# S7G7_footprint_simplified_w_ethernet_v1p.net
KiCad netlist of a schematic drawn in EAGLE
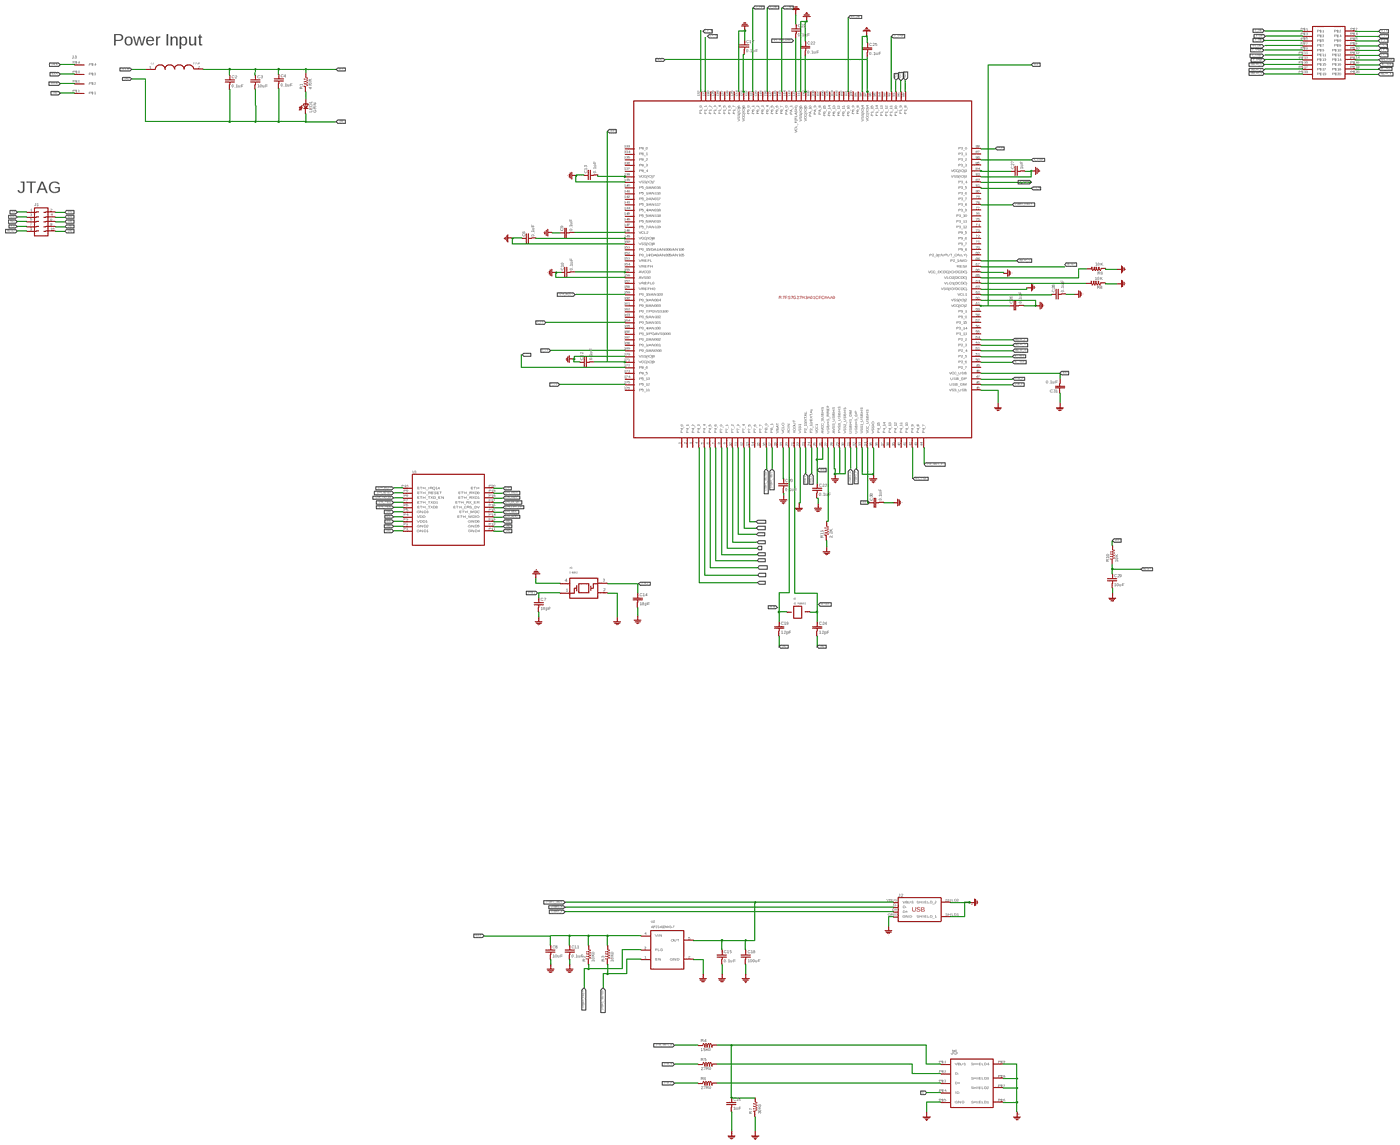
[diagram p0: schematic, sheet 1, overview]
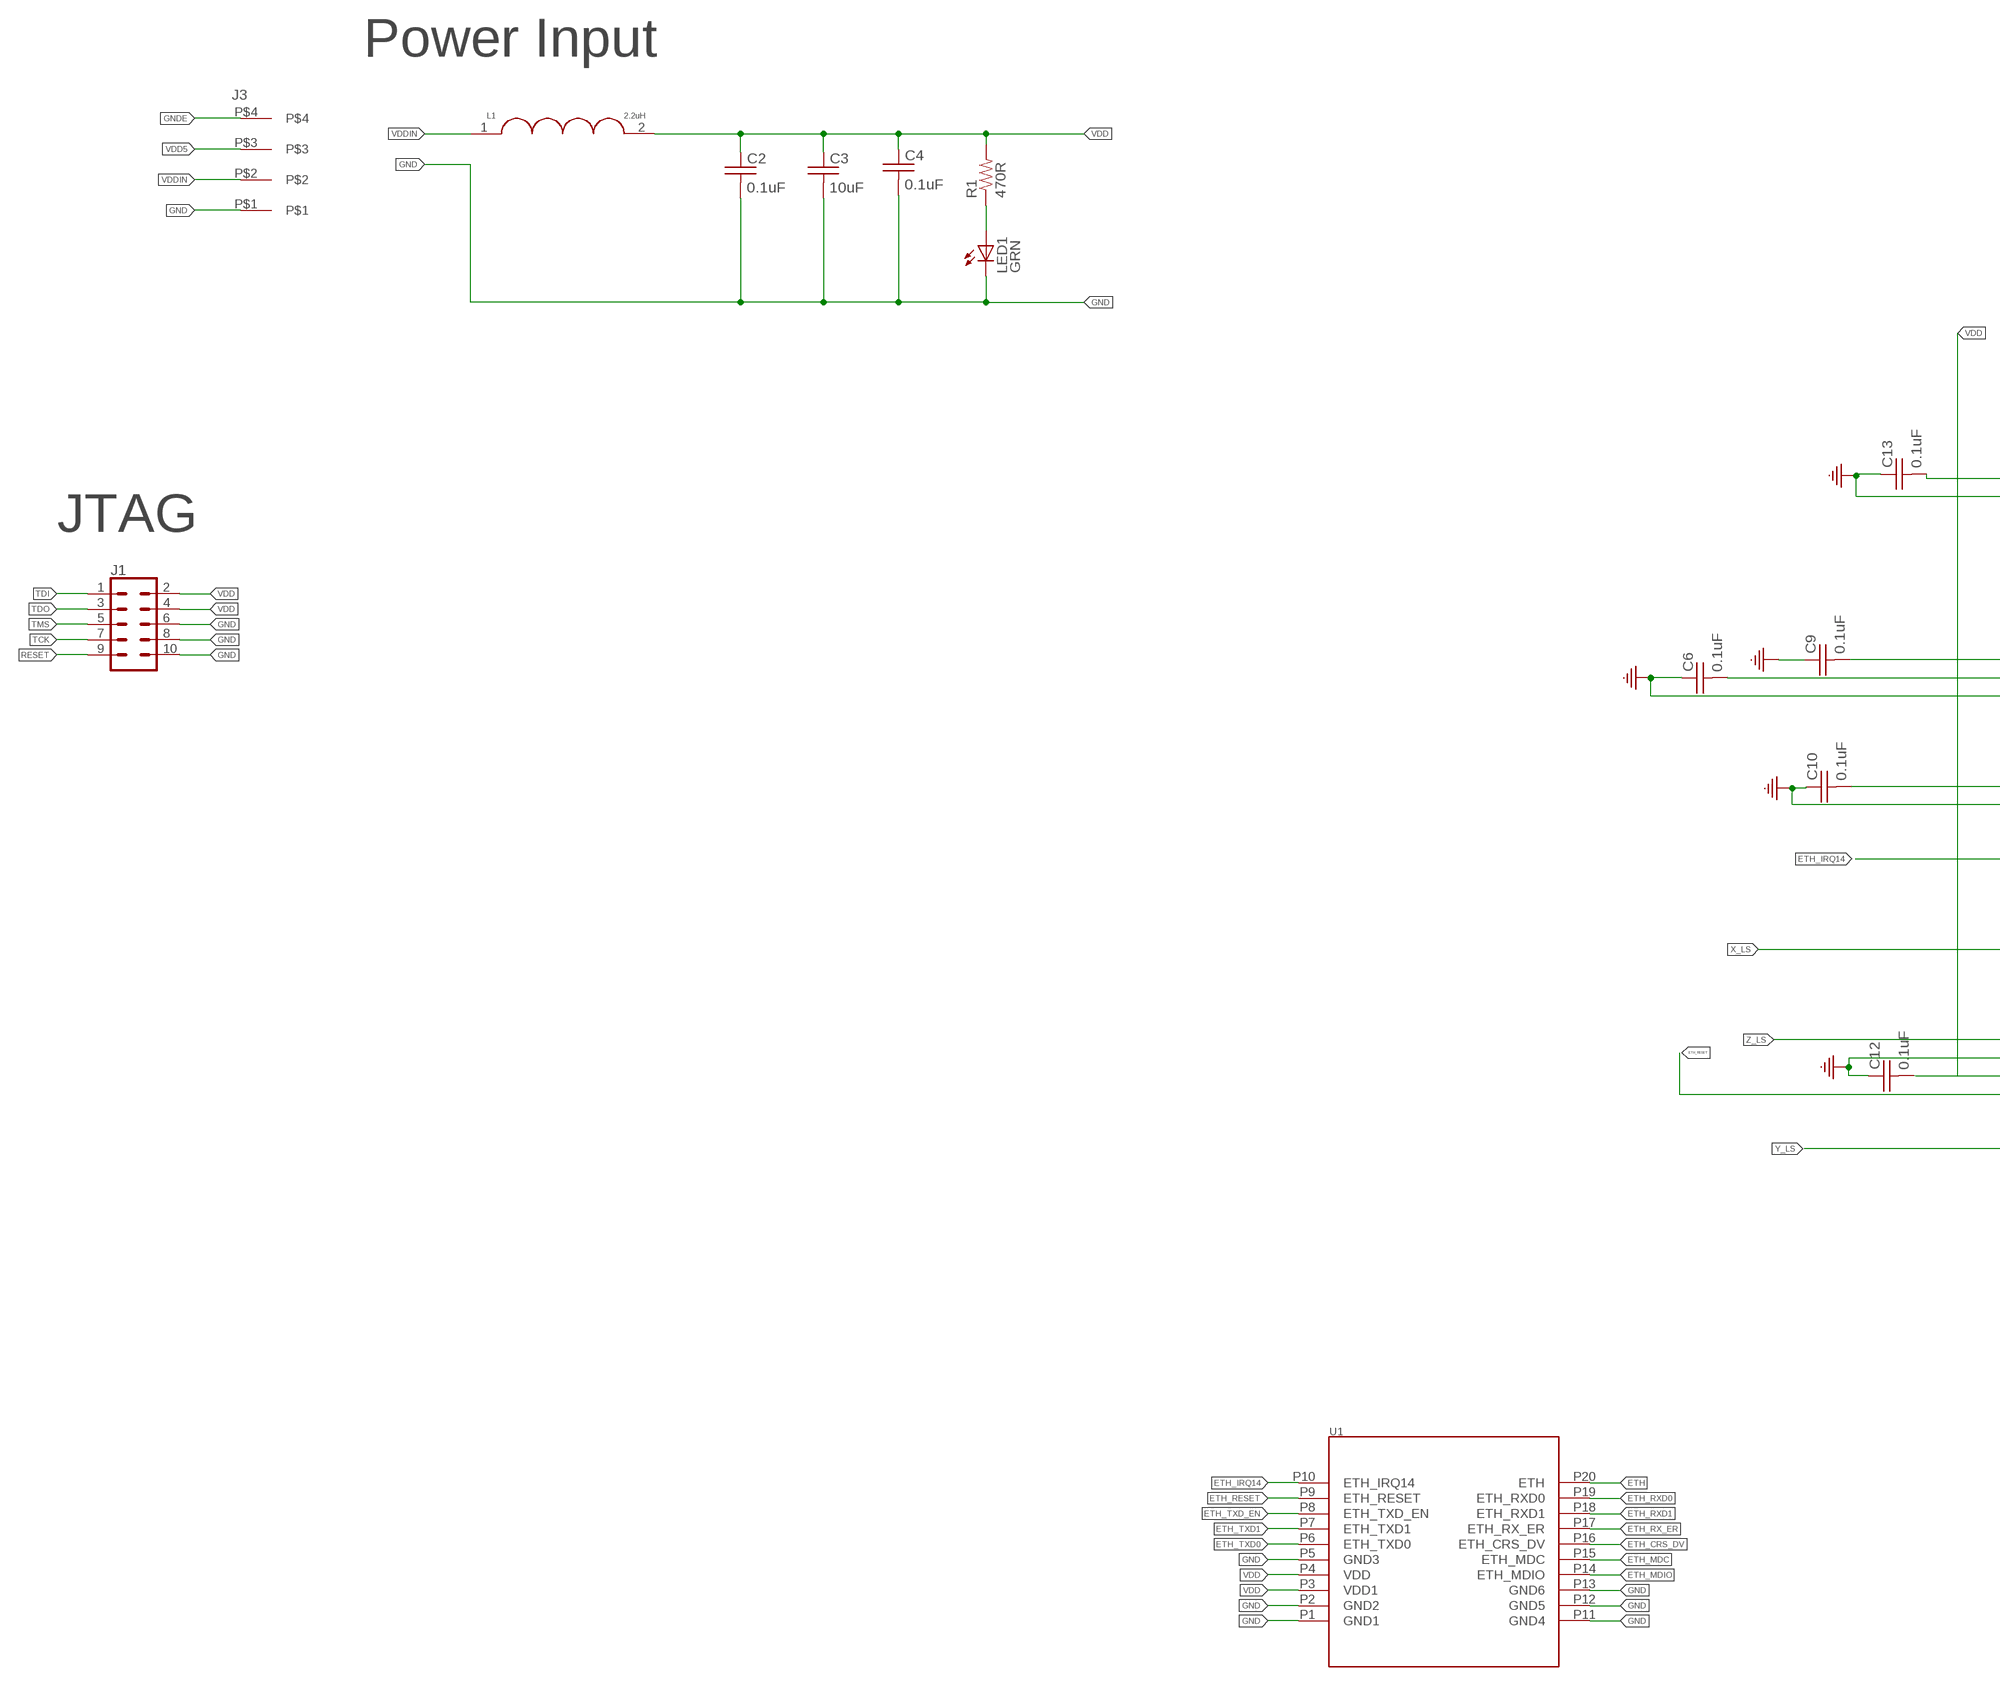
[diagram p1: schematic, sheet 1, part 1 of 4]
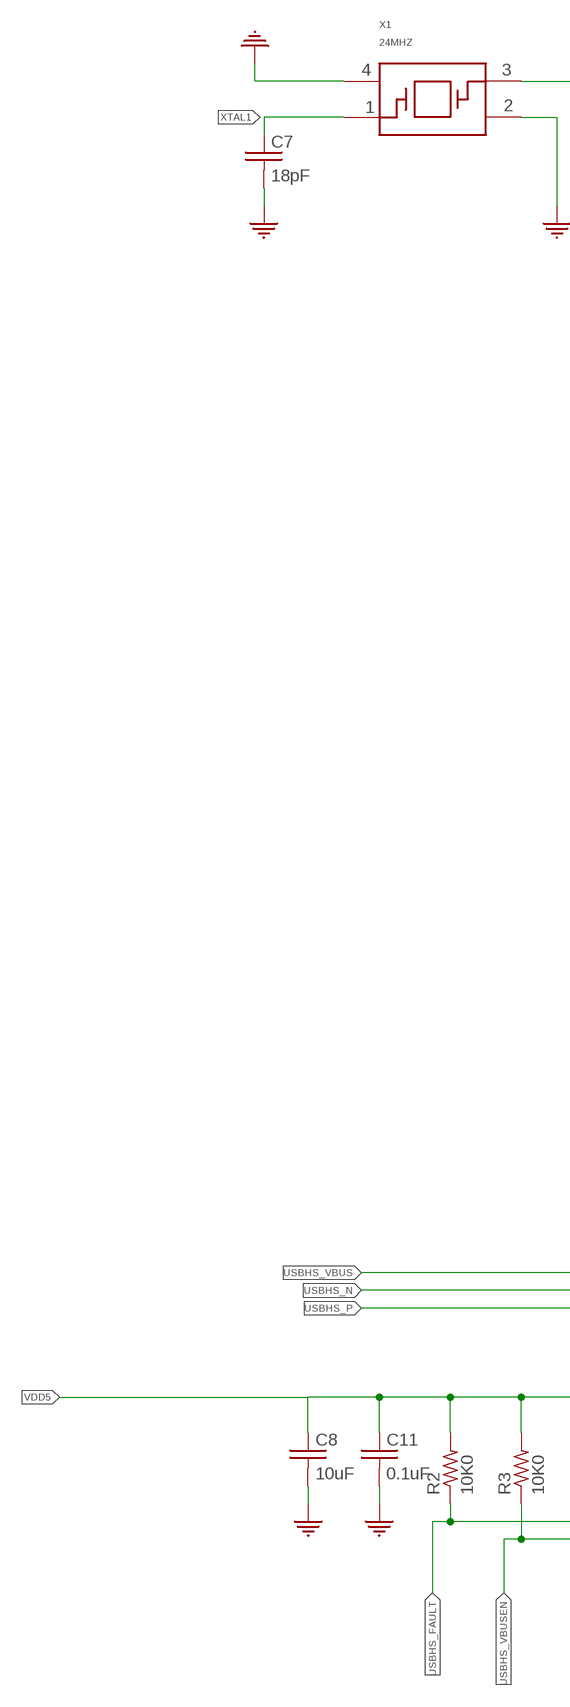
[diagram p2: schematic, sheet 1, part 2 of 4]
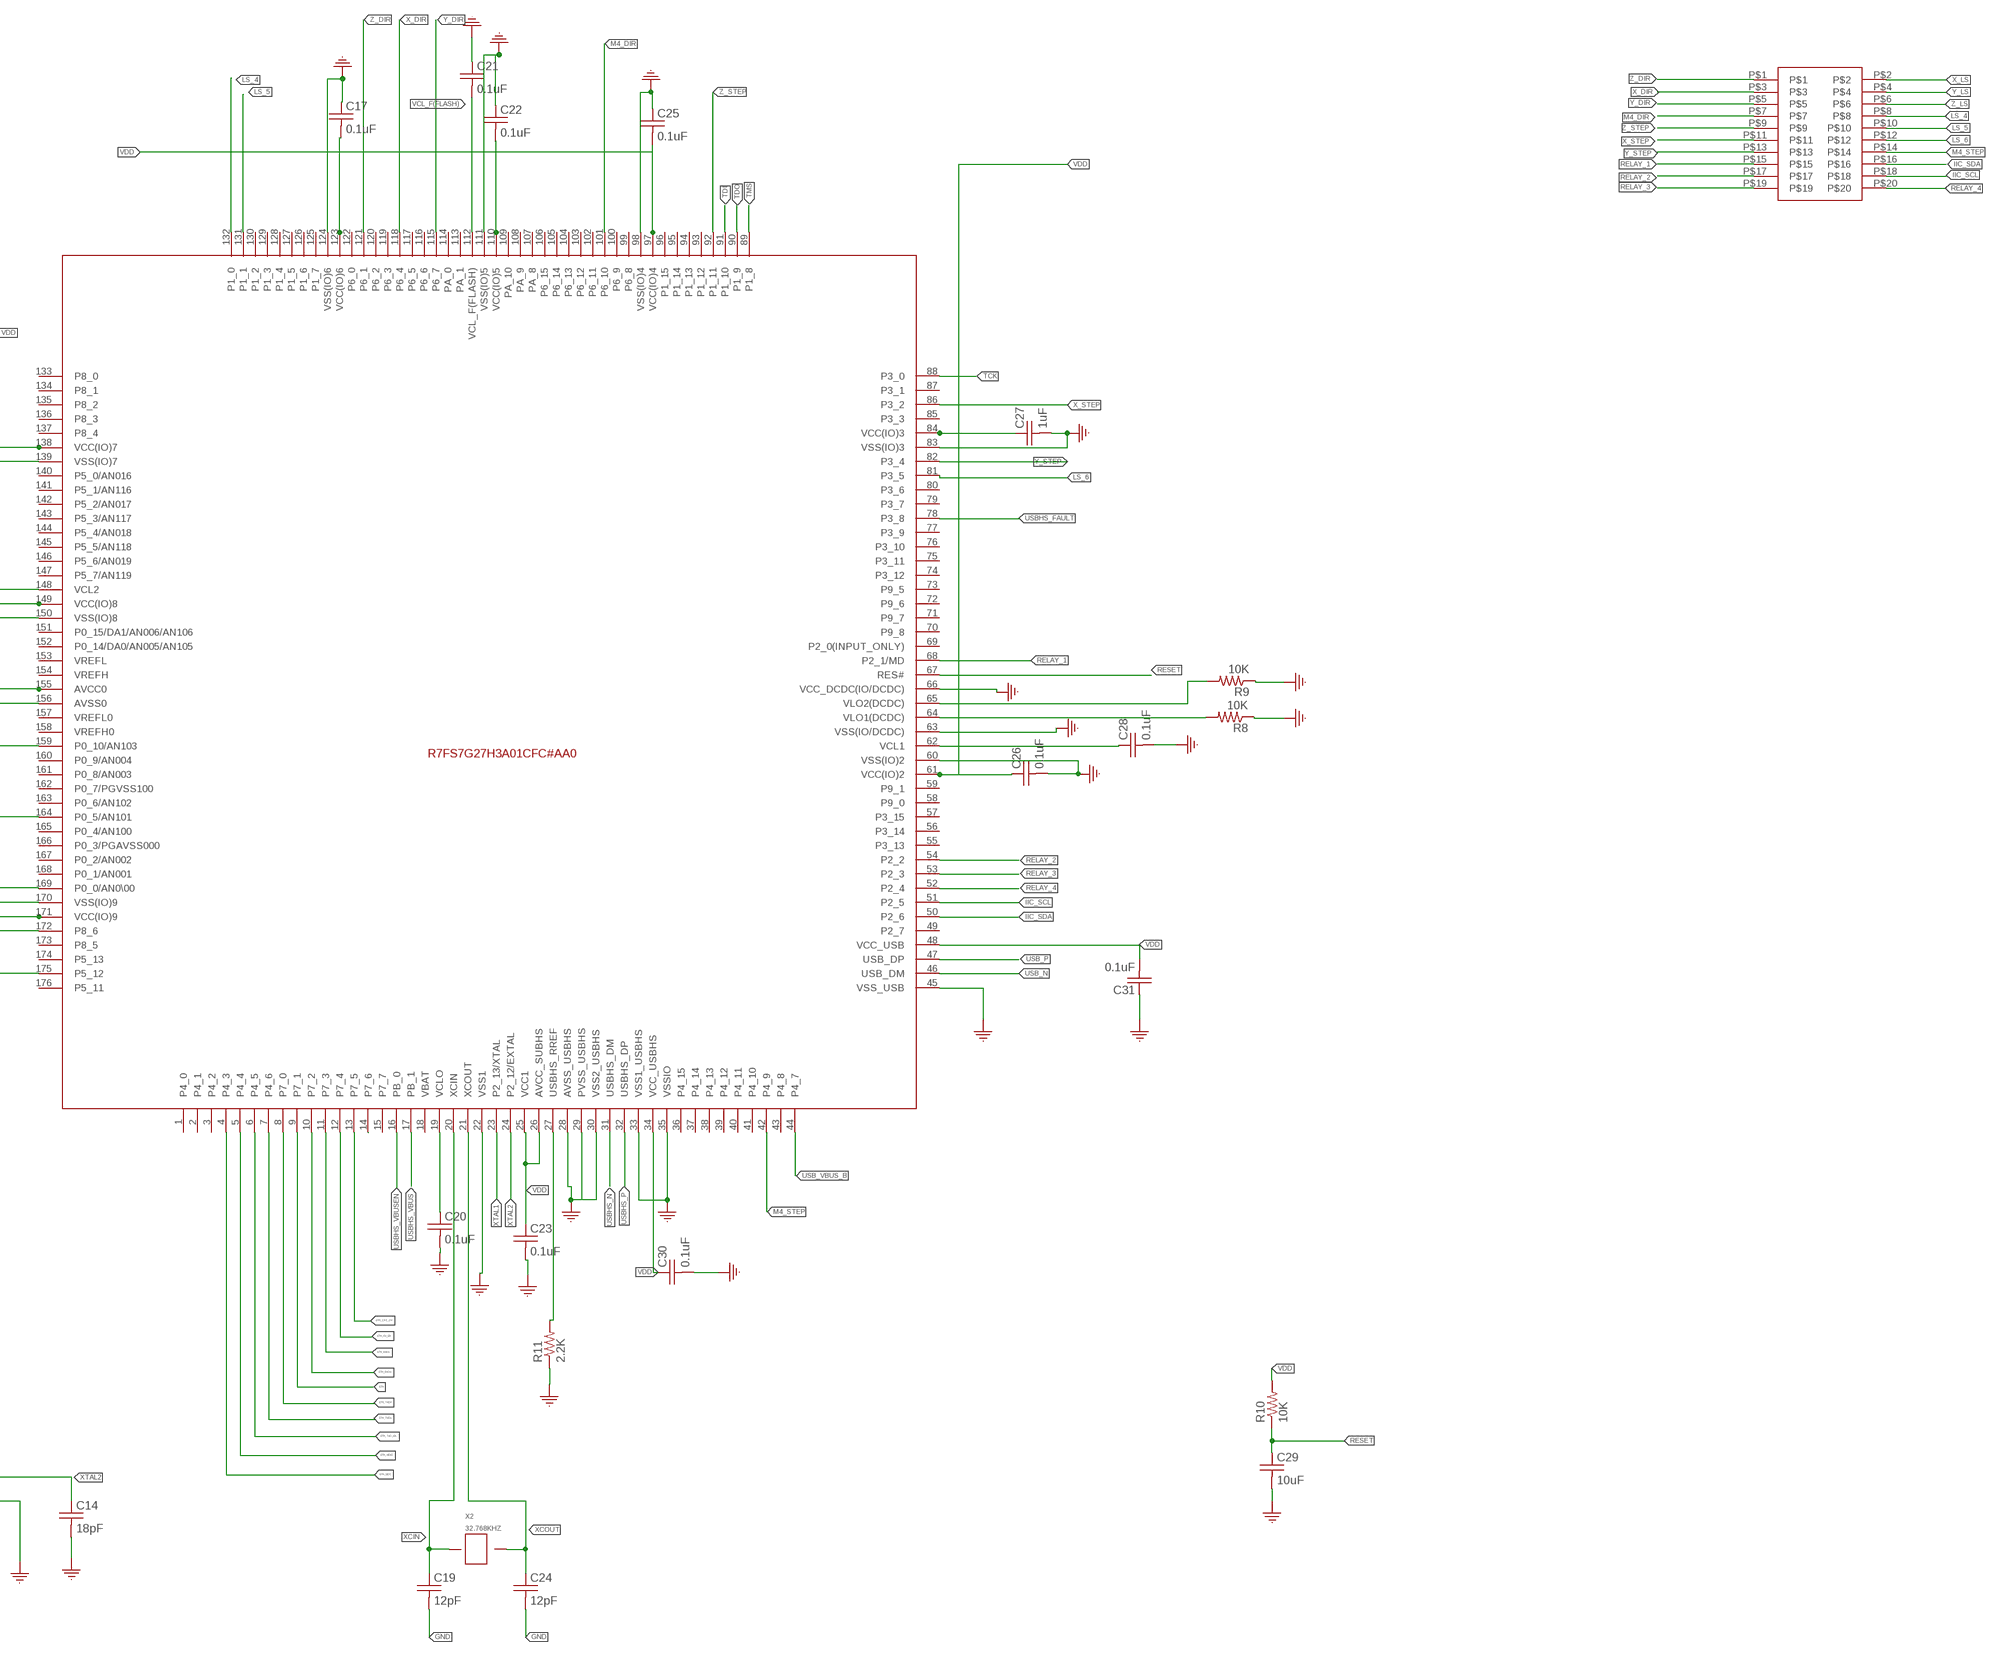
[diagram p3: schematic, sheet 1, part 3 of 4]
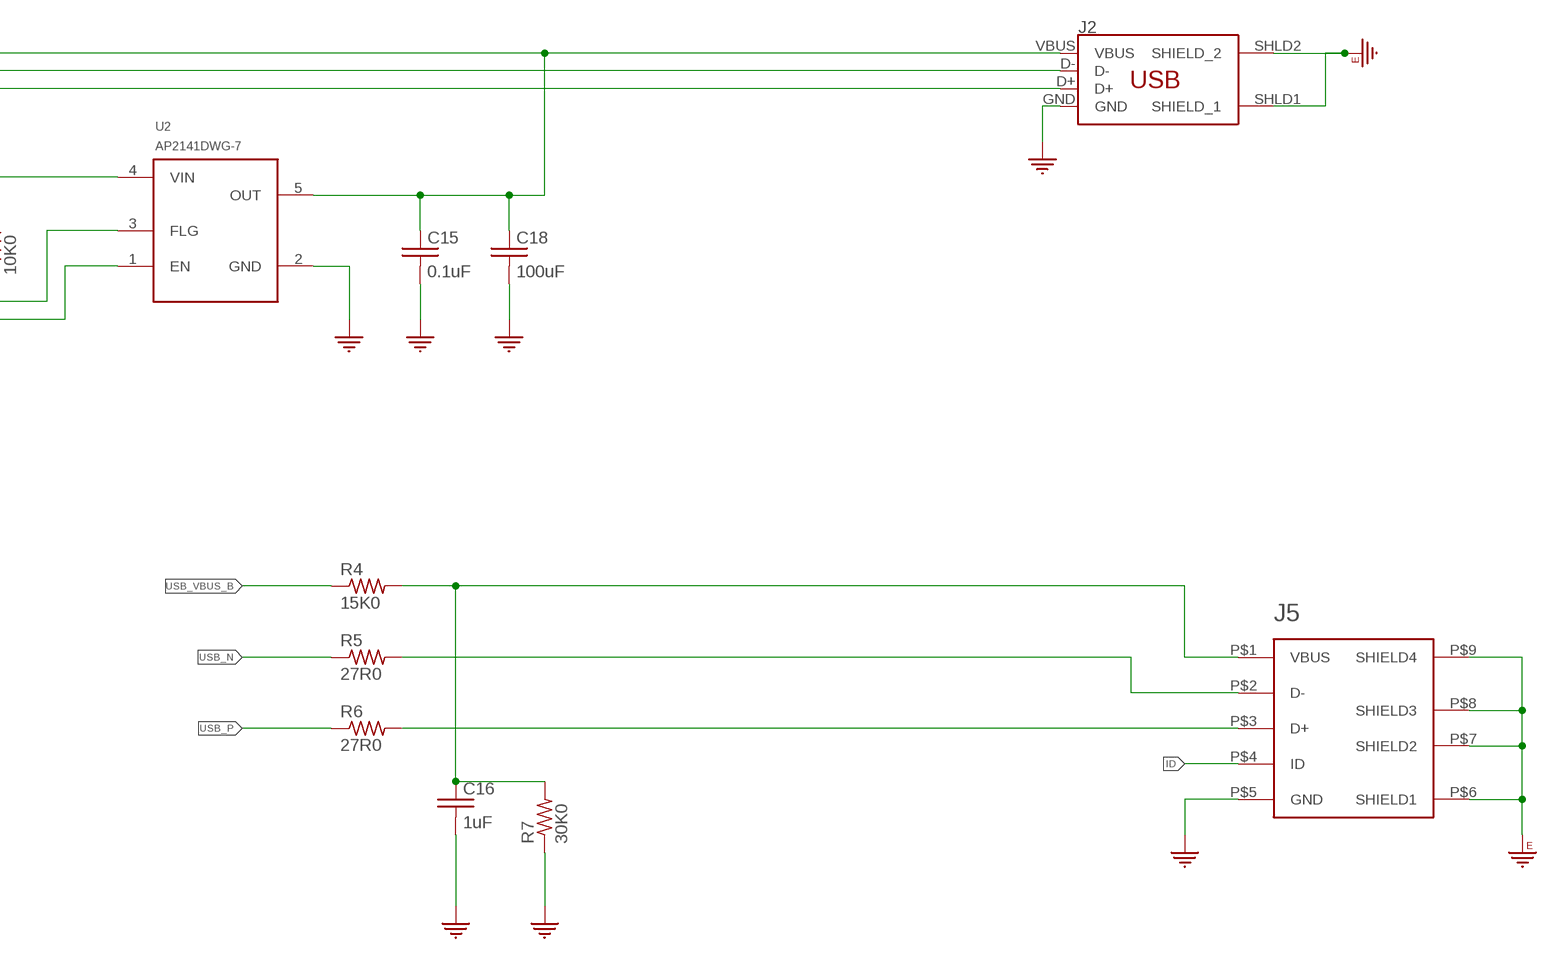
[diagram p4: schematic, sheet 1, part 4 of 4]

(export (version "E")
  (design (tool "Eeschema 10.0.6"))
  (components
    (comp (ref "C2")
      (value "0.1uF")
      (footprint "eagle-import:0402")
      (libsource (lib "eagle-import") (part "C_0402"))
    )
    (comp (ref "C3")
      (value "10uF")
      (footprint "eagle-import:0402")
      (libsource (lib "eagle-import") (part "C_0402"))
    )
    (comp (ref "C4")
      (value "0.1uF")
      (footprint "eagle-import:0402")
      (libsource (lib "eagle-import") (part "C_0402"))
    )
    (comp (ref "C6")
      (value "0.1uF")
      (footprint "eagle-import:0402")
      (libsource (lib "eagle-import") (part "C_0402"))
    )
    (comp (ref "C7")
      (value "18pF")
      (footprint "eagle-import:0402")
      (libsource (lib "eagle-import") (part "C_0402"))
    )
    (comp (ref "C8")
      (value "10uF")
      (footprint "eagle-import:0402")
      (libsource (lib "eagle-import") (part "C_0402"))
    )
    (comp (ref "C9")
      (value "0.1uF")
      (footprint "eagle-import:0402")
      (libsource (lib "eagle-import") (part "C_0402"))
    )
    (comp (ref "C10")
      (value "0.1uF")
      (footprint "eagle-import:0402")
      (libsource (lib "eagle-import") (part "C_0402"))
    )
    (comp (ref "C11")
      (value "0.1uF")
      (footprint "eagle-import:0402")
      (libsource (lib "eagle-import") (part "C_0402"))
    )
    (comp (ref "C12")
      (value "0.1uF")
      (footprint "eagle-import:0402")
      (libsource (lib "eagle-import") (part "C_0402"))
    )
    (comp (ref "C13")
      (value "0.1uF")
      (footprint "eagle-import:0402")
      (libsource (lib "eagle-import") (part "C_0402"))
    )
    (comp (ref "C14")
      (value "18pF")
      (footprint "eagle-import:0402")
      (libsource (lib "eagle-import") (part "C_0402"))
    )
    (comp (ref "C15")
      (value "0.1uF")
      (footprint "eagle-import:0402")
      (libsource (lib "eagle-import") (part "C_0402"))
    )
    (comp (ref "C16")
      (value "1uF")
      (footprint "eagle-import:0402")
      (libsource (lib "eagle-import") (part "C_0402"))
    )
    (comp (ref "C17")
      (value "0.1uF")
      (footprint "eagle-import:0402")
      (libsource (lib "eagle-import") (part "C_0402"))
    )
    (comp (ref "C18")
      (value "100uF")
      (footprint "eagle-import:C1210")
      (libsource (lib "eagle-import") (part "C_1210"))
    )
    (comp (ref "C19")
      (value "12pF")
      (footprint "eagle-import:0402")
      (libsource (lib "eagle-import") (part "C_0402"))
    )
    (comp (ref "C20")
      (value "0.1uF")
      (footprint "eagle-import:0402")
      (libsource (lib "eagle-import") (part "C_0402"))
    )
    (comp (ref "C21")
      (value "0.1uF")
      (footprint "eagle-import:0402")
      (libsource (lib "eagle-import") (part "C_0402"))
    )
    (comp (ref "C22")
      (value "0.1uF")
      (footprint "eagle-import:0402")
      (libsource (lib "eagle-import") (part "C_0402"))
    )
    (comp (ref "C23")
      (value "0.1uF")
      (footprint "eagle-import:0402")
      (libsource (lib "eagle-import") (part "C_0402"))
    )
    (comp (ref "C24")
      (value "12pF")
      (footprint "eagle-import:0402")
      (libsource (lib "eagle-import") (part "C_0402"))
    )
    (comp (ref "C25")
      (value "0.1uF")
      (footprint "eagle-import:0402")
      (libsource (lib "eagle-import") (part "C_0402"))
    )
    (comp (ref "C26")
      (value "0.1uF")
      (footprint "eagle-import:0402")
      (libsource (lib "eagle-import") (part "C_0402"))
    )
    (comp (ref "C27")
      (value "1uF")
      (footprint "eagle-import:0402")
      (libsource (lib "eagle-import") (part "C_0402"))
    )
    (comp (ref "C28")
      (value "0.1uF")
      (footprint "eagle-import:0402")
      (libsource (lib "eagle-import") (part "C_0402"))
    )
    (comp (ref "C29")
      (value "10uF")
      (footprint "eagle-import:0402")
      (libsource (lib "eagle-import") (part "C_0402"))
    )
    (comp (ref "C30")
      (value "0.1uF")
      (footprint "eagle-import:0402")
      (libsource (lib "eagle-import") (part "C_0402"))
    )
    (comp (ref "C31")
      (value "0.1uF")
      (footprint "eagle-import:0402")
      (libsource (lib "eagle-import") (part "C_0402"))
    )
    (comp (ref "J1")
      (value "CONN_05X2PTH")
      (footprint "eagle-import:2X5")
      (libsource (lib "eagle-import") (part "CONN_05X2PTH"))
    )
    (comp (ref "J2")
      (value "USB_A")
      (footprint "eagle-import:USB_A_SMT")
      (libsource (lib "eagle-import") (part "USB_A"))
    )
    (comp (ref "J3")
      (value "3.81MM_1_X_4_RT_ANGLE_PLUG_HEADER")
      (footprint "eagle-import:1X4_3.81MM_PITCH")
      (libsource (lib "eagle-import") (part "3.81MM_1_X_4_RT_ANGLE_PLUG_HEADER"))
    )
    (comp (ref "J4")
      (value "2_X_10_HEADER_GENERIC")
      (footprint "eagle-import:2_X_10_.1_INCH")
      (libsource (lib "eagle-import") (part "2_X_10_HEADER_GENERIC"))
    )
    (comp (ref "J5")
      (value "USB_MICRO-B")
      (footprint "eagle-import:USB_MICRO-B")
      (libsource (lib "eagle-import") (part "USB_MICRO-B"))
    )
    (comp (ref "L1")
      (value "2.2uH")
      (footprint "eagle-import:1008_(2520_METRIC)")
      (libsource (lib "eagle-import") (part "INDUCTOR_1008_2.2_MH_1.3A"))
    )
    (comp (ref "LED1")
      (value "LED_0805_GREEN")
      (footprint "eagle-import:LED_0805_GREEN")
      (libsource (lib "eagle-import") (part "LED_0805_GREEN"))
    )
    (comp (ref "R1")
      (value "470R")
      (footprint "eagle-import:0402")
      (libsource (lib "eagle-import") (part "R_0402"))
    )
    (comp (ref "R2")
      (value "10K0")
      (footprint "eagle-import:0402")
      (libsource (lib "eagle-import") (part "R_0402"))
    )
    (comp (ref "R3")
      (value "10K0")
      (footprint "eagle-import:0402")
      (libsource (lib "eagle-import") (part "R_0402"))
    )
    (comp (ref "R4")
      (value "15K0")
      (footprint "eagle-import:0402")
      (libsource (lib "eagle-import") (part "R_0402"))
    )
    (comp (ref "R5")
      (value "27R0")
      (footprint "eagle-import:0402")
      (libsource (lib "eagle-import") (part "R_0402"))
    )
    (comp (ref "R6")
      (value "27R0")
      (footprint "eagle-import:0402")
      (libsource (lib "eagle-import") (part "R_0402"))
    )
    (comp (ref "R7")
      (value "30K0")
      (footprint "eagle-import:0402")
      (libsource (lib "eagle-import") (part "R_0402"))
    )
    (comp (ref "R8")
      (value "10K")
      (footprint "eagle-import:0402")
      (libsource (lib "eagle-import") (part "R_0402"))
    )
    (comp (ref "R9")
      (value "10K")
      (footprint "eagle-import:0402")
      (libsource (lib "eagle-import") (part "R_0402"))
    )
    (comp (ref "R10")
      (value "10K")
      (footprint "eagle-import:0402")
      (libsource (lib "eagle-import") (part "R_0402"))
    )
    (comp (ref "R11")
      (value "2.2K")
      (footprint "eagle-import:0402")
      (libsource (lib "eagle-import") (part "R_0402"))
    )
    (comp (ref "U1")
      (value "ETHERNET_HAT")
      (footprint "eagle-import:ETHERNET_HAT")
      (libsource (lib "eagle-import") (part "ETHERNET_HAT"))
    )
    (comp (ref "U2")
      (value "AP2141DWG-5")
      (footprint "eagle-import:SOT-23-5")
      (libsource (lib "eagle-import") (part "AP2141DWG-5"))
    )
    (comp (ref "U5")
      (value "S7G2_X_176")
      (footprint "eagle-import:LQFP176_24X24")
      (libsource (lib "eagle-import") (part "S7G2_X_176"))
    )
    (comp (ref "X1")
      (value "24MHZ")
      (footprint "eagle-import:SMD_3225")
      (libsource (lib "eagle-import") (part "XTAL_24_MHZ"))
    )
    (comp (ref "X2")
      (value "32.768KHZ")
      (footprint "eagle-import:SMD_X_2_PADS")
      (libsource (lib "eagle-import") (part "XTAL_32.768KHZ"))
    )
  )
  (nets
    (net (code "1") (name "ETH") (class "Default")
      (node (ref "U1") (pin "P20") (pinfunction "ETH_P20") (pintype "bidirectional"))
      (node (ref "U5") (pin "9") (pinfunction "P7_1_9") (pintype "bidirectional"))
    )
    (net (code "2") (name "ETH_CRS_DV") (class "Default")
      (node (ref "U1") (pin "P16") (pinfunction "ETH_CRS_DV_P16") (pintype "bidirectional"))
      (node (ref "U5") (pin "13") (pinfunction "P7_5_13") (pintype "bidirectional"))
    )
    (net (code "3") (name "ETH_IRQ14") (class "Default")
      (node (ref "U1") (pin "P10") (pinfunction "ETH_IRQ14_P10") (pintype "bidirectional"))
      (node (ref "U5") (pin "159") (pinfunction "P0_10/AN103_159") (pintype "bidirectional"))
    )
    (net (code "4") (name "ETH_MDC") (class "Default")
      (node (ref "U1") (pin "P15") (pinfunction "ETH_MDC_P15") (pintype "bidirectional"))
      (node (ref "U5") (pin "4") (pinfunction "P4_3_4") (pintype "bidirectional"))
    )
    (net (code "5") (name "ETH_MDIO") (class "Default")
      (node (ref "U1") (pin "P14") (pinfunction "ETH_MDIO_P14") (pintype "bidirectional"))
      (node (ref "U5") (pin "5") (pinfunction "P4_4_5") (pintype "bidirectional"))
    )
    (net (code "6") (name "ETH_RESET") (class "Default")
      (node (ref "U1") (pin "P9") (pinfunction "ETH_RESET_P9") (pintype "bidirectional"))
      (node (ref "U5") (pin "172") (pinfunction "P8_6_172") (pintype "bidirectional"))
    )
    (net (code "7") (name "ETH_RXD0") (class "Default")
      (node (ref "U1") (pin "P19") (pinfunction "ETH_RXD0_P19") (pintype "bidirectional"))
      (node (ref "U5") (pin "10") (pinfunction "P7_2_10") (pintype "bidirectional"))
    )
    (net (code "8") (name "ETH_RXD1") (class "Default")
      (node (ref "U1") (pin "P18") (pinfunction "ETH_RXD1_P18") (pintype "bidirectional"))
      (node (ref "U5") (pin "11") (pinfunction "P7_3_11") (pintype "bidirectional"))
    )
    (net (code "9") (name "ETH_RX_ER") (class "Default")
      (node (ref "U1") (pin "P17") (pinfunction "ETH_RX_ER_P17") (pintype "bidirectional"))
      (node (ref "U5") (pin "12") (pinfunction "P7_4_12") (pintype "bidirectional"))
    )
    (net (code "10") (name "ETH_TXD0") (class "Default")
      (node (ref "U1") (pin "P6") (pinfunction "ETH_TXD0_P6") (pintype "bidirectional"))
      (node (ref "U5") (pin "8") (pinfunction "P7_0_8") (pintype "bidirectional"))
    )
    (net (code "11") (name "ETH_TXD1") (class "Default")
      (node (ref "U1") (pin "P7") (pinfunction "ETH_TXD1_P7") (pintype "bidirectional"))
      (node (ref "U5") (pin "7") (pinfunction "P4_6_7") (pintype "bidirectional"))
    )
    (net (code "12") (name "ETH_TXD_EN") (class "Default")
      (node (ref "U1") (pin "P8") (pinfunction "ETH_TXD_EN_P8") (pintype "bidirectional"))
      (node (ref "U5") (pin "6") (pinfunction "P4_5_6") (pintype "bidirectional"))
    )
    (net (code "13") (name "GND") (class "Default")
      (node (ref "C10") (pin "P$1") (pinfunction "1_P$1") (pintype "passive"))
      (node (ref "C11") (pin "P$2") (pinfunction "2_P$2") (pintype "passive"))
      (node (ref "C12") (pin "P$1") (pinfunction "1_P$1") (pintype "passive"))
      (node (ref "C13") (pin "P$1") (pinfunction "1_P$1") (pintype "passive"))
      (node (ref "C14") (pin "P$2") (pinfunction "2_P$2") (pintype "passive"))
      (node (ref "C15") (pin "P$2") (pinfunction "2_P$2") (pintype "passive"))
      (node (ref "C16") (pin "P$2") (pinfunction "2_P$2") (pintype "passive"))
      (node (ref "C17") (pin "P$1") (pinfunction "1_P$1") (pintype "passive"))
      (node (ref "C18") (pin "2") (pinfunction "2_2") (pintype "passive"))
      (node (ref "C19") (pin "P$2") (pinfunction "2_P$2") (pintype "passive"))
      (node (ref "C2") (pin "P$2") (pinfunction "2_P$2") (pintype "passive"))
      (node (ref "C20") (pin "P$2") (pinfunction "2_P$2") (pintype "passive"))
      (node (ref "C21") (pin "P$1") (pinfunction "1_P$1") (pintype "passive"))
      (node (ref "C22") (pin "P$1") (pinfunction "1_P$1") (pintype "passive"))
      (node (ref "C23") (pin "P$2") (pinfunction "2_P$2") (pintype "passive"))
      (node (ref "C24") (pin "P$2") (pinfunction "2_P$2") (pintype "passive"))
      (node (ref "C25") (pin "P$1") (pinfunction "1_P$1") (pintype "passive"))
      (node (ref "C26") (pin "P$2") (pinfunction "2_P$2") (pintype "passive"))
      (node (ref "C27") (pin "P$2") (pinfunction "2_P$2") (pintype "passive"))
      (node (ref "C28") (pin "P$2") (pinfunction "2_P$2") (pintype "passive"))
      (node (ref "C29") (pin "P$2") (pinfunction "2_P$2") (pintype "passive"))
      (node (ref "C3") (pin "P$2") (pinfunction "2_P$2") (pintype "passive"))
      (node (ref "C30") (pin "P$2") (pinfunction "2_P$2") (pintype "passive"))
      (node (ref "C31") (pin "P$1") (pinfunction "1_P$1") (pintype "passive"))
      (node (ref "C4") (pin "P$2") (pinfunction "2_P$2") (pintype "passive"))
      (node (ref "C6") (pin "P$1") (pinfunction "1_P$1") (pintype "passive"))
      (node (ref "C7") (pin "P$2") (pinfunction "2_P$2") (pintype "passive"))
      (node (ref "C8") (pin "P$2") (pinfunction "2_P$2") (pintype "passive"))
      (node (ref "C9") (pin "P$1") (pinfunction "1_P$1") (pintype "passive"))
      (node (ref "J1") (pin "10") (pinfunction "10_10") (pintype "passive"))
      (node (ref "J1") (pin "6") (pinfunction "6_6") (pintype "passive"))
      (node (ref "J1") (pin "8") (pinfunction "8_8") (pintype "passive"))
      (node (ref "J2") (pin "GND") (pinfunction "GND_GND") (pintype "power_in"))
      (node (ref "J3") (pin "P$1") (pinfunction "P$1_P$1") (pintype "bidirectional"))
      (node (ref "J5") (pin "P$5") (pinfunction "GND_P$5") (pintype "bidirectional"))
      (node (ref "LED1") (pin "C") (pinfunction "C_C") (pintype "passive"))
      (node (ref "R11") (pin "P$1") (pinfunction "1_P$1") (pintype "passive"))
      (node (ref "R7") (pin "P$1") (pinfunction "1_P$1") (pintype "passive"))
      (node (ref "R8") (pin "P$1") (pinfunction "1_P$1") (pintype "passive"))
      (node (ref "R9") (pin "P$1") (pinfunction "1_P$1") (pintype "passive"))
      (node (ref "U1") (pin "P1") (pinfunction "GND1_P1") (pintype "bidirectional"))
      (node (ref "U1") (pin "P11") (pinfunction "GND4_P11") (pintype "bidirectional"))
      (node (ref "U1") (pin "P12") (pinfunction "GND5_P12") (pintype "bidirectional"))
      (node (ref "U1") (pin "P13") (pinfunction "GND6_P13") (pintype "bidirectional"))
      (node (ref "U1") (pin "P2") (pinfunction "GND2_P2") (pintype "bidirectional"))
      (node (ref "U1") (pin "P5") (pinfunction "GND3_P5") (pintype "bidirectional"))
      (node (ref "U2") (pin "2") (pinfunction "GND_2") (pintype "input"))
      (node (ref "U5") (pin "111") (pinfunction "VSS(IO)5_111") (pintype "bidirectional"))
      (node (ref "U5") (pin "124") (pinfunction "VSS(IO)6_124") (pintype "bidirectional"))
      (node (ref "U5") (pin "139") (pinfunction "VSS(IO)7_139") (pintype "bidirectional"))
      (node (ref "U5") (pin "150") (pinfunction "VSS(IO)8_150") (pintype "bidirectional"))
      (node (ref "U5") (pin "156") (pinfunction "AVSS0_156") (pintype "bidirectional"))
      (node (ref "U5") (pin "170") (pinfunction "VSS(IO)9_170") (pintype "bidirectional"))
      (node (ref "U5") (pin "22") (pinfunction "VSS1_22") (pintype "bidirectional"))
      (node (ref "U5") (pin "28") (pinfunction "AVSS_USBHS_28") (pintype "bidirectional"))
      (node (ref "U5") (pin "29") (pinfunction "PVSS_USBHS_29") (pintype "bidirectional"))
      (node (ref "U5") (pin "30") (pinfunction "VSS2_USBHS_30") (pintype "bidirectional"))
      (node (ref "U5") (pin "33") (pinfunction "VSS1_USBHS_33") (pintype "bidirectional"))
      (node (ref "U5") (pin "35") (pinfunction "VSSIO_35") (pintype "bidirectional"))
      (node (ref "U5") (pin "45") (pinfunction "VSS_USB_45") (pintype "bidirectional"))
      (node (ref "U5") (pin "60") (pinfunction "VSS(IO)2_60") (pintype "bidirectional"))
      (node (ref "U5") (pin "63") (pinfunction "VSS(IO/DCDC)_63") (pintype "bidirectional"))
      (node (ref "U5") (pin "66") (pinfunction "VCC_DCDC(IO/DCDC)_66") (pintype "bidirectional"))
      (node (ref "U5") (pin "83") (pinfunction "VSS(IO)3_83") (pintype "bidirectional"))
      (node (ref "U5") (pin "98") (pinfunction "VSS(IO)4_98") (pintype "bidirectional"))
      (node (ref "X1") (pin "2") (pinfunction "2_2") (pintype "bidirectional"))
      (node (ref "X1") (pin "4") (pinfunction "4_4") (pintype "bidirectional"))
    )
    (net (code "14") (name "GNDE") (class "Default")
      (node (ref "J2") (pin "SHLD1") (pinfunction "SHIELD_1_SHLD1") (pintype "bidirectional"))
      (node (ref "J2") (pin "SHLD2") (pinfunction "SHIELD_2_SHLD2") (pintype "bidirectional"))
      (node (ref "J3") (pin "P$4") (pinfunction "P$4_P$4") (pintype "bidirectional"))
      (node (ref "J5") (pin "P$6") (pinfunction "SHIELD1_P$6") (pintype "bidirectional"))
      (node (ref "J5") (pin "P$7") (pinfunction "SHIELD2_P$7") (pintype "bidirectional"))
      (node (ref "J5") (pin "P$8") (pinfunction "SHIELD3_P$8") (pintype "bidirectional"))
      (node (ref "J5") (pin "P$9") (pinfunction "SHIELD4_P$9") (pintype "bidirectional"))
    )
    (net (code "15") (name "ID") (class "Default")
      (node (ref "J5") (pin "P$4") (pinfunction "ID_P$4") (pintype "bidirectional"))
    )
    (net (code "16") (name "IIC_SCL") (class "Default")
      (node (ref "J4") (pin "P$18") (pinfunction "P$18_P$18") (pintype "bidirectional"))
      (node (ref "U5") (pin "51") (pinfunction "P2_5_51") (pintype "bidirectional"))
    )
    (net (code "17") (name "IIC_SDA") (class "Default")
      (node (ref "J4") (pin "P$16") (pinfunction "P$16_P$16") (pintype "bidirectional"))
      (node (ref "U5") (pin "50") (pinfunction "P2_6_50") (pintype "bidirectional"))
    )
    (net (code "18") (name "LS_4") (class "Default")
      (node (ref "J4") (pin "P$8") (pinfunction "P$8_P$8") (pintype "bidirectional"))
      (node (ref "U5") (pin "132") (pinfunction "P1_0_132") (pintype "bidirectional"))
    )
    (net (code "19") (name "LS_5") (class "Default")
      (node (ref "J4") (pin "P$10") (pinfunction "P$10_P$10") (pintype "bidirectional"))
      (node (ref "U5") (pin "131") (pinfunction "P1_1_131") (pintype "bidirectional"))
    )
    (net (code "20") (name "LS_6") (class "Default")
      (node (ref "J4") (pin "P$12") (pinfunction "P$12_P$12") (pintype "bidirectional"))
      (node (ref "U5") (pin "81") (pinfunction "P3_5_81") (pintype "bidirectional"))
    )
    (net (code "21") (name "M4_DIR") (class "Default")
      (node (ref "J4") (pin "P$7") (pinfunction "P$7_P$7") (pintype "bidirectional"))
      (node (ref "U5") (pin "101") (pinfunction "P6_10_101") (pintype "bidirectional"))
    )
    (net (code "22") (name "M4_STEP") (class "Default")
      (node (ref "J4") (pin "P$14") (pinfunction "P$14_P$14") (pintype "bidirectional"))
      (node (ref "U5") (pin "42") (pinfunction "P4_9_42") (pintype "bidirectional"))
    )
    (net (code "23") (name "Net-(C9-2)") (class "Default")
      (node (ref "C9") (pin "P$2") (pinfunction "2_P$2") (pintype "passive"))
      (node (ref "U5") (pin "148") (pinfunction "VCL2_148") (pintype "bidirectional"))
    )
    (net (code "24") (name "Net-(C16-1)") (class "Default")
      (node (ref "C16") (pin "P$1") (pinfunction "1_P$1") (pintype "passive"))
      (node (ref "J5") (pin "P$1") (pinfunction "VBUS_P$1") (pintype "bidirectional"))
      (node (ref "R4") (pin "P$2") (pinfunction "2_P$2") (pintype "passive"))
      (node (ref "R7") (pin "P$2") (pinfunction "2_P$2") (pintype "passive"))
    )
    (net (code "25") (name "Net-(C20-1)") (class "Default")
      (node (ref "C20") (pin "P$1") (pinfunction "1_P$1") (pintype "passive"))
      (node (ref "U5") (pin "19") (pinfunction "VCLO_19") (pintype "bidirectional"))
    )
    (net (code "26") (name "Net-(C28-1)") (class "Default")
      (node (ref "C28") (pin "P$1") (pinfunction "1_P$1") (pintype "passive"))
      (node (ref "U5") (pin "62") (pinfunction "VCL1_62") (pintype "bidirectional"))
    )
    (net (code "27") (name "Net-(J5-D+)") (class "Default")
      (node (ref "J5") (pin "P$3") (pinfunction "D+_P$3") (pintype "bidirectional"))
      (node (ref "R6") (pin "P$2") (pinfunction "2_P$2") (pintype "passive"))
    )
    (net (code "28") (name "Net-(J5-D-)") (class "Default")
      (node (ref "J5") (pin "P$2") (pinfunction "D-_P$2") (pintype "bidirectional"))
      (node (ref "R5") (pin "P$2") (pinfunction "2_P$2") (pintype "passive"))
    )
    (net (code "29") (name "Net-(R1-1)") (class "Default")
      (node (ref "LED1") (pin "A") (pinfunction "A_A") (pintype "passive"))
      (node (ref "R1") (pin "P$1") (pinfunction "1_P$1") (pintype "passive"))
    )
    (net (code "30") (name "Net-(R8-2)") (class "Default")
      (node (ref "R8") (pin "P$2") (pinfunction "2_P$2") (pintype "passive"))
      (node (ref "U5") (pin "64") (pinfunction "VLO1(DCDC)_64") (pintype "bidirectional"))
    )
    (net (code "31") (name "Net-(R9-2)") (class "Default")
      (node (ref "R9") (pin "P$2") (pinfunction "2_P$2") (pintype "passive"))
      (node (ref "U5") (pin "65") (pinfunction "VLO2(DCDC)_65") (pintype "bidirectional"))
    )
    (net (code "32") (name "Net-(R11-2)") (class "Default")
      (node (ref "R11") (pin "P$2") (pinfunction "2_P$2") (pintype "passive"))
      (node (ref "U5") (pin "27") (pinfunction "USBHS_RREF_27") (pintype "bidirectional"))
    )
    (net (code "33") (name "RELAY_1") (class "Default")
      (node (ref "J4") (pin "P$15") (pinfunction "P$15_P$15") (pintype "bidirectional"))
      (node (ref "U5") (pin "68") (pinfunction "P2_1/MD_68") (pintype "bidirectional"))
    )
    (net (code "34") (name "RELAY_2") (class "Default")
      (node (ref "J4") (pin "P$17") (pinfunction "P$17_P$17") (pintype "bidirectional"))
      (node (ref "U5") (pin "54") (pinfunction "P2_2_54") (pintype "bidirectional"))
    )
    (net (code "35") (name "RELAY_3") (class "Default")
      (node (ref "J4") (pin "P$19") (pinfunction "P$19_P$19") (pintype "bidirectional"))
      (node (ref "U5") (pin "53") (pinfunction "P2_3_53") (pintype "bidirectional"))
    )
    (net (code "36") (name "RELAY_4") (class "Default")
      (node (ref "J4") (pin "P$20") (pinfunction "P$20_P$20") (pintype "bidirectional"))
      (node (ref "U5") (pin "52") (pinfunction "P2_4_52") (pintype "bidirectional"))
    )
    (net (code "37") (name "RESET") (class "Default")
      (node (ref "C29") (pin "P$1") (pinfunction "1_P$1") (pintype "passive"))
      (node (ref "J1") (pin "9") (pinfunction "9_9") (pintype "passive"))
      (node (ref "R10") (pin "P$1") (pinfunction "1_P$1") (pintype "passive"))
      (node (ref "U5") (pin "67") (pinfunction "RES#_67") (pintype "bidirectional"))
    )
    (net (code "38") (name "TCK") (class "Default")
      (node (ref "J1") (pin "7") (pinfunction "7_7") (pintype "passive"))
      (node (ref "U5") (pin "88") (pinfunction "P3_0_88") (pintype "bidirectional"))
    )
    (net (code "39") (name "TDI") (class "Default")
      (node (ref "J1") (pin "1") (pinfunction "1_1") (pintype "passive"))
      (node (ref "U5") (pin "91") (pinfunction "P1_10_91") (pintype "bidirectional"))
    )
    (net (code "40") (name "TDO") (class "Default")
      (node (ref "J1") (pin "3") (pinfunction "3_3") (pintype "passive"))
      (node (ref "U5") (pin "90") (pinfunction "P1_9_90") (pintype "bidirectional"))
    )
    (net (code "41") (name "TMS") (class "Default")
      (node (ref "J1") (pin "5") (pinfunction "5_5") (pintype "passive"))
      (node (ref "U5") (pin "89") (pinfunction "P1_8_89") (pintype "bidirectional"))
    )
    (net (code "42") (name "USBHS_FAULT") (class "Default")
      (node (ref "R2") (pin "P$1") (pinfunction "1_P$1") (pintype "passive"))
      (node (ref "U2") (pin "3") (pinfunction "FLG_3") (pintype "input"))
      (node (ref "U5") (pin "78") (pinfunction "P3_8_78") (pintype "bidirectional"))
    )
    (net (code "43") (name "USBHS_N") (class "Default")
      (node (ref "J2") (pin "D-") (pinfunction "D-_D-") (pintype "bidirectional"))
      (node (ref "U5") (pin "31") (pinfunction "USBHS_DM_31") (pintype "bidirectional"))
    )
    (net (code "44") (name "USBHS_P") (class "Default")
      (node (ref "J2") (pin "D+") (pinfunction "D+_D+") (pintype "bidirectional"))
      (node (ref "U5") (pin "32") (pinfunction "USBHS_DP_32") (pintype "bidirectional"))
    )
    (net (code "45") (name "USBHS_VBUS") (class "Default")
      (node (ref "C15") (pin "P$1") (pinfunction "1_P$1") (pintype "passive"))
      (node (ref "C18") (pin "1") (pinfunction "1_1") (pintype "passive"))
      (node (ref "J2") (pin "VBUS") (pinfunction "VBUS_VBUS") (pintype "power_in"))
      (node (ref "U2") (pin "5") (pinfunction "OUT_5") (pintype "input"))
      (node (ref "U5") (pin "17") (pinfunction "PB_1_17") (pintype "bidirectional"))
    )
    (net (code "46") (name "USBHS_VBUSEN") (class "Default")
      (node (ref "R3") (pin "P$1") (pinfunction "1_P$1") (pintype "passive"))
      (node (ref "U2") (pin "1") (pinfunction "EN_1") (pintype "input"))
      (node (ref "U5") (pin "16") (pinfunction "PB_0_16") (pintype "bidirectional"))
    )
    (net (code "47") (name "USB_N") (class "Default")
      (node (ref "R5") (pin "P$1") (pinfunction "1_P$1") (pintype "passive"))
      (node (ref "U5") (pin "46") (pinfunction "USB_DM_46") (pintype "bidirectional"))
    )
    (net (code "48") (name "USB_P") (class "Default")
      (node (ref "R6") (pin "P$1") (pinfunction "1_P$1") (pintype "passive"))
      (node (ref "U5") (pin "47") (pinfunction "USB_DP_47") (pintype "bidirectional"))
    )
    (net (code "49") (name "USB_VBUS_B") (class "Default")
      (node (ref "R4") (pin "P$1") (pinfunction "1_P$1") (pintype "passive"))
      (node (ref "U5") (pin "44") (pinfunction "P4_7_44") (pintype "bidirectional"))
    )
    (net (code "50") (name "VCL_F(FLASH)") (class "Default")
      (node (ref "C21") (pin "P$2") (pinfunction "2_P$2") (pintype "passive"))
      (node (ref "U5") (pin "112") (pinfunction "VCL_F(FLASH)_112") (pintype "bidirectional"))
    )
    (net (code "51") (name "VDD") (class "Default")
      (node (ref "C10") (pin "P$2") (pinfunction "2_P$2") (pintype "passive"))
      (node (ref "C12") (pin "P$2") (pinfunction "2_P$2") (pintype "passive"))
      (node (ref "C13") (pin "P$2") (pinfunction "2_P$2") (pintype "passive"))
      (node (ref "C17") (pin "P$2") (pinfunction "2_P$2") (pintype "passive"))
      (node (ref "C2") (pin "P$1") (pinfunction "1_P$1") (pintype "passive"))
      (node (ref "C22") (pin "P$2") (pinfunction "2_P$2") (pintype "passive"))
      (node (ref "C23") (pin "P$1") (pinfunction "1_P$1") (pintype "passive"))
      (node (ref "C25") (pin "P$2") (pinfunction "2_P$2") (pintype "passive"))
      (node (ref "C26") (pin "P$1") (pinfunction "1_P$1") (pintype "passive"))
      (node (ref "C27") (pin "P$1") (pinfunction "1_P$1") (pintype "passive"))
      (node (ref "C3") (pin "P$1") (pinfunction "1_P$1") (pintype "passive"))
      (node (ref "C30") (pin "P$1") (pinfunction "1_P$1") (pintype "passive"))
      (node (ref "C31") (pin "P$2") (pinfunction "2_P$2") (pintype "passive"))
      (node (ref "C4") (pin "P$1") (pinfunction "1_P$1") (pintype "passive"))
      (node (ref "C6") (pin "P$2") (pinfunction "2_P$2") (pintype "passive"))
      (node (ref "J1") (pin "2") (pinfunction "2_2") (pintype "passive"))
      (node (ref "J1") (pin "4") (pinfunction "4_4") (pintype "passive"))
      (node (ref "L1") (pin "2") (pinfunction "P$2_2") (pintype "bidirectional"))
      (node (ref "R1") (pin "P$2") (pinfunction "2_P$2") (pintype "passive"))
      (node (ref "R10") (pin "P$2") (pinfunction "2_P$2") (pintype "passive"))
      (node (ref "U1") (pin "P3") (pinfunction "VDD1_P3") (pintype "bidirectional"))
      (node (ref "U1") (pin "P4") (pinfunction "VDD_P4") (pintype "bidirectional"))
      (node (ref "U5") (pin "110") (pinfunction "VCC(IO)5_110") (pintype "bidirectional"))
      (node (ref "U5") (pin "123") (pinfunction "VCC(IO)6_123") (pintype "bidirectional"))
      (node (ref "U5") (pin "138") (pinfunction "VCC(IO)7_138") (pintype "bidirectional"))
      (node (ref "U5") (pin "149") (pinfunction "VCC(IO)8_149") (pintype "bidirectional"))
      (node (ref "U5") (pin "155") (pinfunction "AVCC0_155") (pintype "bidirectional"))
      (node (ref "U5") (pin "171") (pinfunction "VCC(IO)9_171") (pintype "bidirectional"))
      (node (ref "U5") (pin "25") (pinfunction "VCC1_25") (pintype "bidirectional"))
      (node (ref "U5") (pin "26") (pinfunction "AVCC_SUBHS_26") (pintype "bidirectional"))
      (node (ref "U5") (pin "34") (pinfunction "VCC_USBHS_34") (pintype "bidirectional"))
      (node (ref "U5") (pin "48") (pinfunction "VCC_USB_48") (pintype "bidirectional"))
      (node (ref "U5") (pin "61") (pinfunction "VCC(IO)2_61") (pintype "bidirectional"))
      (node (ref "U5") (pin "84") (pinfunction "VCC(IO)3_84") (pintype "bidirectional"))
      (node (ref "U5") (pin "97") (pinfunction "VCC(IO)4_97") (pintype "bidirectional"))
    )
    (net (code "52") (name "VDD5") (class "Default")
      (node (ref "C11") (pin "P$1") (pinfunction "1_P$1") (pintype "passive"))
      (node (ref "C8") (pin "P$1") (pinfunction "1_P$1") (pintype "passive"))
      (node (ref "J3") (pin "P$3") (pinfunction "P$3_P$3") (pintype "bidirectional"))
      (node (ref "R2") (pin "P$2") (pinfunction "2_P$2") (pintype "passive"))
      (node (ref "R3") (pin "P$2") (pinfunction "2_P$2") (pintype "passive"))
      (node (ref "U2") (pin "4") (pinfunction "VIN_4") (pintype "input"))
    )
    (net (code "53") (name "VDDIN") (class "Default")
      (node (ref "J3") (pin "P$2") (pinfunction "P$2_P$2") (pintype "bidirectional"))
      (node (ref "L1") (pin "1") (pinfunction "P$1_1") (pintype "bidirectional"))
    )
    (net (code "54") (name "XCIN") (class "Default")
      (node (ref "C19") (pin "P$1") (pinfunction "1_P$1") (pintype "passive"))
      (node (ref "U5") (pin "20") (pinfunction "XCIN_20") (pintype "bidirectional"))
      (node (ref "X2") (pin "P$1") (pinfunction "P$1_P$1") (pintype "bidirectional"))
    )
    (net (code "55") (name "XCOUT") (class "Default")
      (node (ref "C24") (pin "P$1") (pinfunction "1_P$1") (pintype "passive"))
      (node (ref "U5") (pin "21") (pinfunction "XCOUT_21") (pintype "bidirectional"))
      (node (ref "X2") (pin "P$2") (pinfunction "P$2_P$2") (pintype "bidirectional"))
    )
    (net (code "56") (name "XTAL1") (class "Default")
      (node (ref "C7") (pin "P$1") (pinfunction "1_P$1") (pintype "passive"))
      (node (ref "U5") (pin "23") (pinfunction "P2_13/XTAL_23") (pintype "bidirectional"))
      (node (ref "X1") (pin "1") (pinfunction "1_1") (pintype "bidirectional"))
    )
    (net (code "57") (name "XTAL2") (class "Default")
      (node (ref "C14") (pin "P$1") (pinfunction "1_P$1") (pintype "passive"))
      (node (ref "U5") (pin "24") (pinfunction "P2_12/EXTAL_24") (pintype "bidirectional"))
      (node (ref "X1") (pin "3") (pinfunction "3_3") (pintype "bidirectional"))
    )
    (net (code "58") (name "X_DIR") (class "Default")
      (node (ref "J4") (pin "P$3") (pinfunction "P$3_P$3") (pintype "bidirectional"))
      (node (ref "U5") (pin "118") (pinfunction "P6_4_118") (pintype "bidirectional"))
    )
    (net (code "59") (name "X_LS") (class "Default")
      (node (ref "J4") (pin "P$2") (pinfunction "P$2_P$2") (pintype "bidirectional"))
      (node (ref "U5") (pin "164") (pinfunction "P0_5/AN101_164") (pintype "bidirectional"))
    )
    (net (code "60") (name "X_STEP") (class "Default")
      (node (ref "J4") (pin "P$11") (pinfunction "P$11_P$11") (pintype "bidirectional"))
      (node (ref "U5") (pin "86") (pinfunction "P3_2_86") (pintype "bidirectional"))
    )
    (net (code "61") (name "Y_DIR") (class "Default")
      (node (ref "J4") (pin "P$5") (pinfunction "P$5_P$5") (pintype "bidirectional"))
      (node (ref "U5") (pin "115") (pinfunction "P6_7_115") (pintype "bidirectional"))
    )
    (net (code "62") (name "Y_LS") (class "Default")
      (node (ref "J4") (pin "P$4") (pinfunction "P$4_P$4") (pintype "bidirectional"))
      (node (ref "U5") (pin "175") (pinfunction "P5_12_175") (pintype "bidirectional"))
    )
    (net (code "63") (name "Y_STEP") (class "Default")
      (node (ref "J4") (pin "P$13") (pinfunction "P$13_P$13") (pintype "bidirectional"))
      (node (ref "U5") (pin "82") (pinfunction "P3_4_82") (pintype "bidirectional"))
    )
    (net (code "64") (name "Z_DIR") (class "Default")
      (node (ref "J4") (pin "P$1") (pinfunction "P$1_P$1") (pintype "bidirectional"))
      (node (ref "U5") (pin "121") (pinfunction "P6_1_121") (pintype "bidirectional"))
    )
    (net (code "65") (name "Z_LS") (class "Default")
      (node (ref "J4") (pin "P$6") (pinfunction "P$6_P$6") (pintype "bidirectional"))
      (node (ref "U5") (pin "169") (pinfunction "P0_0/AN0\\00_169") (pintype "bidirectional"))
    )
    (net (code "66") (name "Z_STEP") (class "Default")
      (node (ref "J4") (pin "P$9") (pinfunction "P$9_P$9") (pintype "bidirectional"))
      (node (ref "U5") (pin "92") (pinfunction "P1_11_92") (pintype "bidirectional"))
    )
    (net (code "67") (name "unconnected-(U5-P0_1{slash}AN001-Pad168)") (class "Default")
      (node (ref "U5") (pin "168") (pinfunction "P0_1/AN001_168") (pintype "bidirectional"))
    )
    (net (code "68") (name "unconnected-(U5-P0_2{slash}AN002-Pad167)") (class "Default")
      (node (ref "U5") (pin "167") (pinfunction "P0_2/AN002_167") (pintype "bidirectional"))
    )
    (net (code "69") (name "unconnected-(U5-P0_3{slash}PGAVSS000-Pad166)") (class "Default")
      (node (ref "U5") (pin "166") (pinfunction "P0_3/PGAVSS000_166") (pintype "bidirectional"))
    )
    (net (code "70") (name "unconnected-(U5-P0_4{slash}AN100-Pad165)") (class "Default")
      (node (ref "U5") (pin "165") (pinfunction "P0_4/AN100_165") (pintype "bidirectional"))
    )
    (net (code "71") (name "unconnected-(U5-P0_6{slash}AN102-Pad163)") (class "Default")
      (node (ref "U5") (pin "163") (pinfunction "P0_6/AN102_163") (pintype "bidirectional"))
    )
    (net (code "72") (name "unconnected-(U5-P0_7{slash}PGVSS100-Pad162)") (class "Default")
      (node (ref "U5") (pin "162") (pinfunction "P0_7/PGVSS100_162") (pintype "bidirectional"))
    )
    (net (code "73") (name "unconnected-(U5-P0_8{slash}AN003-Pad161)") (class "Default")
      (node (ref "U5") (pin "161") (pinfunction "P0_8/AN003_161") (pintype "bidirectional"))
    )
    (net (code "74") (name "unconnected-(U5-P0_9{slash}AN004-Pad160)") (class "Default")
      (node (ref "U5") (pin "160") (pinfunction "P0_9/AN004_160") (pintype "bidirectional"))
    )
    (net (code "75") (name "unconnected-(U5-P0_14{slash}DA0{slash}AN005{slash}AN105-Pad152)") (class "Default")
      (node (ref "U5") (pin "152") (pinfunction "P0_14/DA0/AN005/AN105_152") (pintype "bidirectional"))
    )
    (net (code "76") (name "unconnected-(U5-P0_15{slash}DA1{slash}AN006{slash}AN106-Pad151)") (class "Default")
      (node (ref "U5") (pin "151") (pinfunction "P0_15/DA1/AN006/AN106_151") (pintype "bidirectional"))
    )
    (net (code "77") (name "unconnected-(U5-P1_2-Pad130)") (class "Default")
      (node (ref "U5") (pin "130") (pinfunction "P1_2_130") (pintype "bidirectional"))
    )
    (net (code "78") (name "unconnected-(U5-P1_3-Pad129)") (class "Default")
      (node (ref "U5") (pin "129") (pinfunction "P1_3_129") (pintype "bidirectional"))
    )
    (net (code "79") (name "unconnected-(U5-P1_4-Pad128)") (class "Default")
      (node (ref "U5") (pin "128") (pinfunction "P1_4_128") (pintype "bidirectional"))
    )
    (net (code "80") (name "unconnected-(U5-P1_5-Pad127)") (class "Default")
      (node (ref "U5") (pin "127") (pinfunction "P1_5_127") (pintype "bidirectional"))
    )
    (net (code "81") (name "unconnected-(U5-P1_6-Pad126)") (class "Default")
      (node (ref "U5") (pin "126") (pinfunction "P1_6_126") (pintype "bidirectional"))
    )
    (net (code "82") (name "unconnected-(U5-P1_7-Pad125)") (class "Default")
      (node (ref "U5") (pin "125") (pinfunction "P1_7_125") (pintype "bidirectional"))
    )
    (net (code "83") (name "unconnected-(U5-P1_12-Pad93)") (class "Default")
      (node (ref "U5") (pin "93") (pinfunction "P1_12_93") (pintype "bidirectional"))
    )
    (net (code "84") (name "unconnected-(U5-P1_13-Pad94)") (class "Default")
      (node (ref "U5") (pin "94") (pinfunction "P1_13_94") (pintype "bidirectional"))
    )
    (net (code "85") (name "unconnected-(U5-P1_14-Pad95)") (class "Default")
      (node (ref "U5") (pin "95") (pinfunction "P1_14_95") (pintype "bidirectional"))
    )
    (net (code "86") (name "unconnected-(U5-P1_15-Pad96)") (class "Default")
      (node (ref "U5") (pin "96") (pinfunction "P1_15_96") (pintype "bidirectional"))
    )
    (net (code "87") (name "unconnected-(U5-P2_0(INPUT_ONLY)-Pad69)") (class "Default")
      (node (ref "U5") (pin "69") (pinfunction "P2_0(INPUT_ONLY)_69") (pintype "bidirectional"))
    )
    (net (code "88") (name "unconnected-(U5-P2_7-Pad49)") (class "Default")
      (node (ref "U5") (pin "49") (pinfunction "P2_7_49") (pintype "bidirectional"))
    )
    (net (code "89") (name "unconnected-(U5-P3_1-Pad87)") (class "Default")
      (node (ref "U5") (pin "87") (pinfunction "P3_1_87") (pintype "bidirectional"))
    )
    (net (code "90") (name "unconnected-(U5-P3_3-Pad85)") (class "Default")
      (node (ref "U5") (pin "85") (pinfunction "P3_3_85") (pintype "bidirectional"))
    )
    (net (code "91") (name "unconnected-(U5-P3_6-Pad80)") (class "Default")
      (node (ref "U5") (pin "80") (pinfunction "P3_6_80") (pintype "bidirectional"))
    )
    (net (code "92") (name "unconnected-(U5-P3_7-Pad79)") (class "Default")
      (node (ref "U5") (pin "79") (pinfunction "P3_7_79") (pintype "bidirectional"))
    )
    (net (code "93") (name "unconnected-(U5-P3_9-Pad77)") (class "Default")
      (node (ref "U5") (pin "77") (pinfunction "P3_9_77") (pintype "bidirectional"))
    )
    (net (code "94") (name "unconnected-(U5-P3_10-Pad76)") (class "Default")
      (node (ref "U5") (pin "76") (pinfunction "P3_10_76") (pintype "bidirectional"))
    )
    (net (code "95") (name "unconnected-(U5-P3_11-Pad75)") (class "Default")
      (node (ref "U5") (pin "75") (pinfunction "P3_11_75") (pintype "bidirectional"))
    )
    (net (code "96") (name "unconnected-(U5-P3_12-Pad74)") (class "Default")
      (node (ref "U5") (pin "74") (pinfunction "P3_12_74") (pintype "bidirectional"))
    )
    (net (code "97") (name "unconnected-(U5-P3_13-Pad55)") (class "Default")
      (node (ref "U5") (pin "55") (pinfunction "P3_13_55") (pintype "bidirectional"))
    )
    (net (code "98") (name "unconnected-(U5-P3_14-Pad56)") (class "Default")
      (node (ref "U5") (pin "56") (pinfunction "P3_14_56") (pintype "bidirectional"))
    )
    (net (code "99") (name "unconnected-(U5-P3_15-Pad57)") (class "Default")
      (node (ref "U5") (pin "57") (pinfunction "P3_15_57") (pintype "bidirectional"))
    )
    (net (code "100") (name "unconnected-(U5-P4_0-Pad1)") (class "Default")
      (node (ref "U5") (pin "1") (pinfunction "P4_0_1") (pintype "bidirectional"))
    )
    (net (code "101") (name "unconnected-(U5-P4_1-Pad2)") (class "Default")
      (node (ref "U5") (pin "2") (pinfunction "P4_1_2") (pintype "bidirectional"))
    )
    (net (code "102") (name "unconnected-(U5-P4_2-Pad3)") (class "Default")
      (node (ref "U5") (pin "3") (pinfunction "P4_2_3") (pintype "bidirectional"))
    )
    (net (code "103") (name "unconnected-(U5-P4_8-Pad43)") (class "Default")
      (node (ref "U5") (pin "43") (pinfunction "P4_8_43") (pintype "bidirectional"))
    )
    (net (code "104") (name "unconnected-(U5-P4_10-Pad41)") (class "Default")
      (node (ref "U5") (pin "41") (pinfunction "P4_10_41") (pintype "bidirectional"))
    )
    (net (code "105") (name "unconnected-(U5-P4_11-Pad40)") (class "Default")
      (node (ref "U5") (pin "40") (pinfunction "P4_11_40") (pintype "bidirectional"))
    )
    (net (code "106") (name "unconnected-(U5-P4_12-Pad39)") (class "Default")
      (node (ref "U5") (pin "39") (pinfunction "P4_12_39") (pintype "bidirectional"))
    )
    (net (code "107") (name "unconnected-(U5-P4_13-Pad38)") (class "Default")
      (node (ref "U5") (pin "38") (pinfunction "P4_13_38") (pintype "bidirectional"))
    )
    (net (code "108") (name "unconnected-(U5-P4_14-Pad37)") (class "Default")
      (node (ref "U5") (pin "37") (pinfunction "P4_14_37") (pintype "bidirectional"))
    )
    (net (code "109") (name "unconnected-(U5-P4_15-Pad36)") (class "Default")
      (node (ref "U5") (pin "36") (pinfunction "P4_15_36") (pintype "bidirectional"))
    )
    (net (code "110") (name "unconnected-(U5-P5_0{slash}AN016-Pad140)") (class "Default")
      (node (ref "U5") (pin "140") (pinfunction "P5_0/AN016_140") (pintype "bidirectional"))
    )
    (net (code "111") (name "unconnected-(U5-P5_1{slash}AN116-Pad141)") (class "Default")
      (node (ref "U5") (pin "141") (pinfunction "P5_1/AN116_141") (pintype "bidirectional"))
    )
    (net (code "112") (name "unconnected-(U5-P5_2{slash}AN017-Pad142)") (class "Default")
      (node (ref "U5") (pin "142") (pinfunction "P5_2/AN017_142") (pintype "bidirectional"))
    )
    (net (code "113") (name "unconnected-(U5-P5_3{slash}AN117-Pad143)") (class "Default")
      (node (ref "U5") (pin "143") (pinfunction "P5_3/AN117_143") (pintype "bidirectional"))
    )
    (net (code "114") (name "unconnected-(U5-P5_4{slash}AN018-Pad144)") (class "Default")
      (node (ref "U5") (pin "144") (pinfunction "P5_4/AN018_144") (pintype "bidirectional"))
    )
    (net (code "115") (name "unconnected-(U5-P5_5{slash}AN118-Pad145)") (class "Default")
      (node (ref "U5") (pin "145") (pinfunction "P5_5/AN118_145") (pintype "bidirectional"))
    )
    (net (code "116") (name "unconnected-(U5-P5_6{slash}AN019-Pad146)") (class "Default")
      (node (ref "U5") (pin "146") (pinfunction "P5_6/AN019_146") (pintype "bidirectional"))
    )
    (net (code "117") (name "unconnected-(U5-P5_7{slash}AN119-Pad147)") (class "Default")
      (node (ref "U5") (pin "147") (pinfunction "P5_7/AN119_147") (pintype "bidirectional"))
    )
    (net (code "118") (name "unconnected-(U5-P5_11-Pad176)") (class "Default")
      (node (ref "U5") (pin "176") (pinfunction "P5_11_176") (pintype "bidirectional"))
    )
    (net (code "119") (name "unconnected-(U5-P5_13-Pad174)") (class "Default")
      (node (ref "U5") (pin "174") (pinfunction "P5_13_174") (pintype "bidirectional"))
    )
    (net (code "120") (name "unconnected-(U5-P6_0-Pad122)") (class "Default")
      (node (ref "U5") (pin "122") (pinfunction "P6_0_122") (pintype "bidirectional"))
    )
    (net (code "121") (name "unconnected-(U5-P6_2-Pad120)") (class "Default")
      (node (ref "U5") (pin "120") (pinfunction "P6_2_120") (pintype "bidirectional"))
    )
    (net (code "122") (name "unconnected-(U5-P6_3-Pad119)") (class "Default")
      (node (ref "U5") (pin "119") (pinfunction "P6_3_119") (pintype "bidirectional"))
    )
    (net (code "123") (name "unconnected-(U5-P6_5-Pad117)") (class "Default")
      (node (ref "U5") (pin "117") (pinfunction "P6_5_117") (pintype "bidirectional"))
    )
    (net (code "124") (name "unconnected-(U5-P6_6-Pad116)") (class "Default")
      (node (ref "U5") (pin "116") (pinfunction "P6_6_116") (pintype "bidirectional"))
    )
    (net (code "125") (name "unconnected-(U5-P6_8-Pad99)") (class "Default")
      (node (ref "U5") (pin "99") (pinfunction "P6_8_99") (pintype "bidirectional"))
    )
    (net (code "126") (name "unconnected-(U5-P6_9-Pad100)") (class "Default")
      (node (ref "U5") (pin "100") (pinfunction "P6_9_100") (pintype "bidirectional"))
    )
    (net (code "127") (name "unconnected-(U5-P6_11-Pad102)") (class "Default")
      (node (ref "U5") (pin "102") (pinfunction "P6_11_102") (pintype "bidirectional"))
    )
    (net (code "128") (name "unconnected-(U5-P6_12-Pad103)") (class "Default")
      (node (ref "U5") (pin "103") (pinfunction "P6_12_103") (pintype "bidirectional"))
    )
    (net (code "129") (name "unconnected-(U5-P6_13-Pad104)") (class "Default")
      (node (ref "U5") (pin "104") (pinfunction "P6_13_104") (pintype "bidirectional"))
    )
    (net (code "130") (name "unconnected-(U5-P6_14-Pad105)") (class "Default")
      (node (ref "U5") (pin "105") (pinfunction "P6_14_105") (pintype "bidirectional"))
    )
    (net (code "131") (name "unconnected-(U5-P6_15-Pad106)") (class "Default")
      (node (ref "U5") (pin "106") (pinfunction "P6_15_106") (pintype "bidirectional"))
    )
    (net (code "132") (name "unconnected-(U5-P7_6-Pad14)") (class "Default")
      (node (ref "U5") (pin "14") (pinfunction "P7_6_14") (pintype "bidirectional"))
    )
    (net (code "133") (name "unconnected-(U5-P7_7-Pad15)") (class "Default")
      (node (ref "U5") (pin "15") (pinfunction "P7_7_15") (pintype "bidirectional"))
    )
    (net (code "134") (name "unconnected-(U5-P8_0-Pad133)") (class "Default")
      (node (ref "U5") (pin "133") (pinfunction "P8_0_133") (pintype "bidirectional"))
    )
    (net (code "135") (name "unconnected-(U5-P8_1-Pad134)") (class "Default")
      (node (ref "U5") (pin "134") (pinfunction "P8_1_134") (pintype "bidirectional"))
    )
    (net (code "136") (name "unconnected-(U5-P8_2-Pad135)") (class "Default")
      (node (ref "U5") (pin "135") (pinfunction "P8_2_135") (pintype "bidirectional"))
    )
    (net (code "137") (name "unconnected-(U5-P8_3-Pad136)") (class "Default")
      (node (ref "U5") (pin "136") (pinfunction "P8_3_136") (pintype "bidirectional"))
    )
    (net (code "138") (name "unconnected-(U5-P8_4-Pad137)") (class "Default")
      (node (ref "U5") (pin "137") (pinfunction "P8_4_137") (pintype "bidirectional"))
    )
    (net (code "139") (name "unconnected-(U5-P8_5-Pad173)") (class "Default")
      (node (ref "U5") (pin "173") (pinfunction "P8_5_173") (pintype "bidirectional"))
    )
    (net (code "140") (name "unconnected-(U5-P9_0-Pad58)") (class "Default")
      (node (ref "U5") (pin "58") (pinfunction "P9_0_58") (pintype "bidirectional"))
    )
    (net (code "141") (name "unconnected-(U5-P9_1-Pad59)") (class "Default")
      (node (ref "U5") (pin "59") (pinfunction "P9_1_59") (pintype "bidirectional"))
    )
    (net (code "142") (name "unconnected-(U5-P9_5-Pad73)") (class "Default")
      (node (ref "U5") (pin "73") (pinfunction "P9_5_73") (pintype "bidirectional"))
    )
    (net (code "143") (name "unconnected-(U5-P9_6-Pad72)") (class "Default")
      (node (ref "U5") (pin "72") (pinfunction "P9_6_72") (pintype "bidirectional"))
    )
    (net (code "144") (name "unconnected-(U5-P9_7-Pad71)") (class "Default")
      (node (ref "U5") (pin "71") (pinfunction "P9_7_71") (pintype "bidirectional"))
    )
    (net (code "145") (name "unconnected-(U5-P9_8-Pad70)") (class "Default")
      (node (ref "U5") (pin "70") (pinfunction "P9_8_70") (pintype "bidirectional"))
    )
    (net (code "146") (name "unconnected-(U5-PA_0-Pad114)") (class "Default")
      (node (ref "U5") (pin "114") (pinfunction "PA_0_114") (pintype "bidirectional"))
    )
    (net (code "147") (name "unconnected-(U5-PA_1-Pad113)") (class "Default")
      (node (ref "U5") (pin "113") (pinfunction "PA_1_113") (pintype "bidirectional"))
    )
    (net (code "148") (name "unconnected-(U5-PA_8-Pad107)") (class "Default")
      (node (ref "U5") (pin "107") (pinfunction "PA_8_107") (pintype "bidirectional"))
    )
    (net (code "149") (name "unconnected-(U5-PA_9-Pad108)") (class "Default")
      (node (ref "U5") (pin "108") (pinfunction "PA_9_108") (pintype "bidirectional"))
    )
    (net (code "150") (name "unconnected-(U5-PA_10-Pad109)") (class "Default")
      (node (ref "U5") (pin "109") (pinfunction "PA_10_109") (pintype "bidirectional"))
    )
    (net (code "151") (name "unconnected-(U5-VBAT-Pad18)") (class "Default")
      (node (ref "U5") (pin "18") (pinfunction "VBAT_18") (pintype "bidirectional"))
    )
    (net (code "152") (name "unconnected-(U5-VREFH-Pad154)") (class "Default")
      (node (ref "U5") (pin "154") (pinfunction "VREFH_154") (pintype "bidirectional"))
    )
    (net (code "153") (name "unconnected-(U5-VREFH0-Pad158)") (class "Default")
      (node (ref "U5") (pin "158") (pinfunction "VREFH0_158") (pintype "bidirectional"))
    )
    (net (code "154") (name "unconnected-(U5-VREFL-Pad153)") (class "Default")
      (node (ref "U5") (pin "153") (pinfunction "VREFL_153") (pintype "bidirectional"))
    )
    (net (code "155") (name "unconnected-(U5-VREFL0-Pad157)") (class "Default")
      (node (ref "U5") (pin "157") (pinfunction "VREFL0_157") (pintype "bidirectional"))
    )
  )
)
